# project_full_hardware.net
KiCad netlist of a schematic drawn in EAGLE
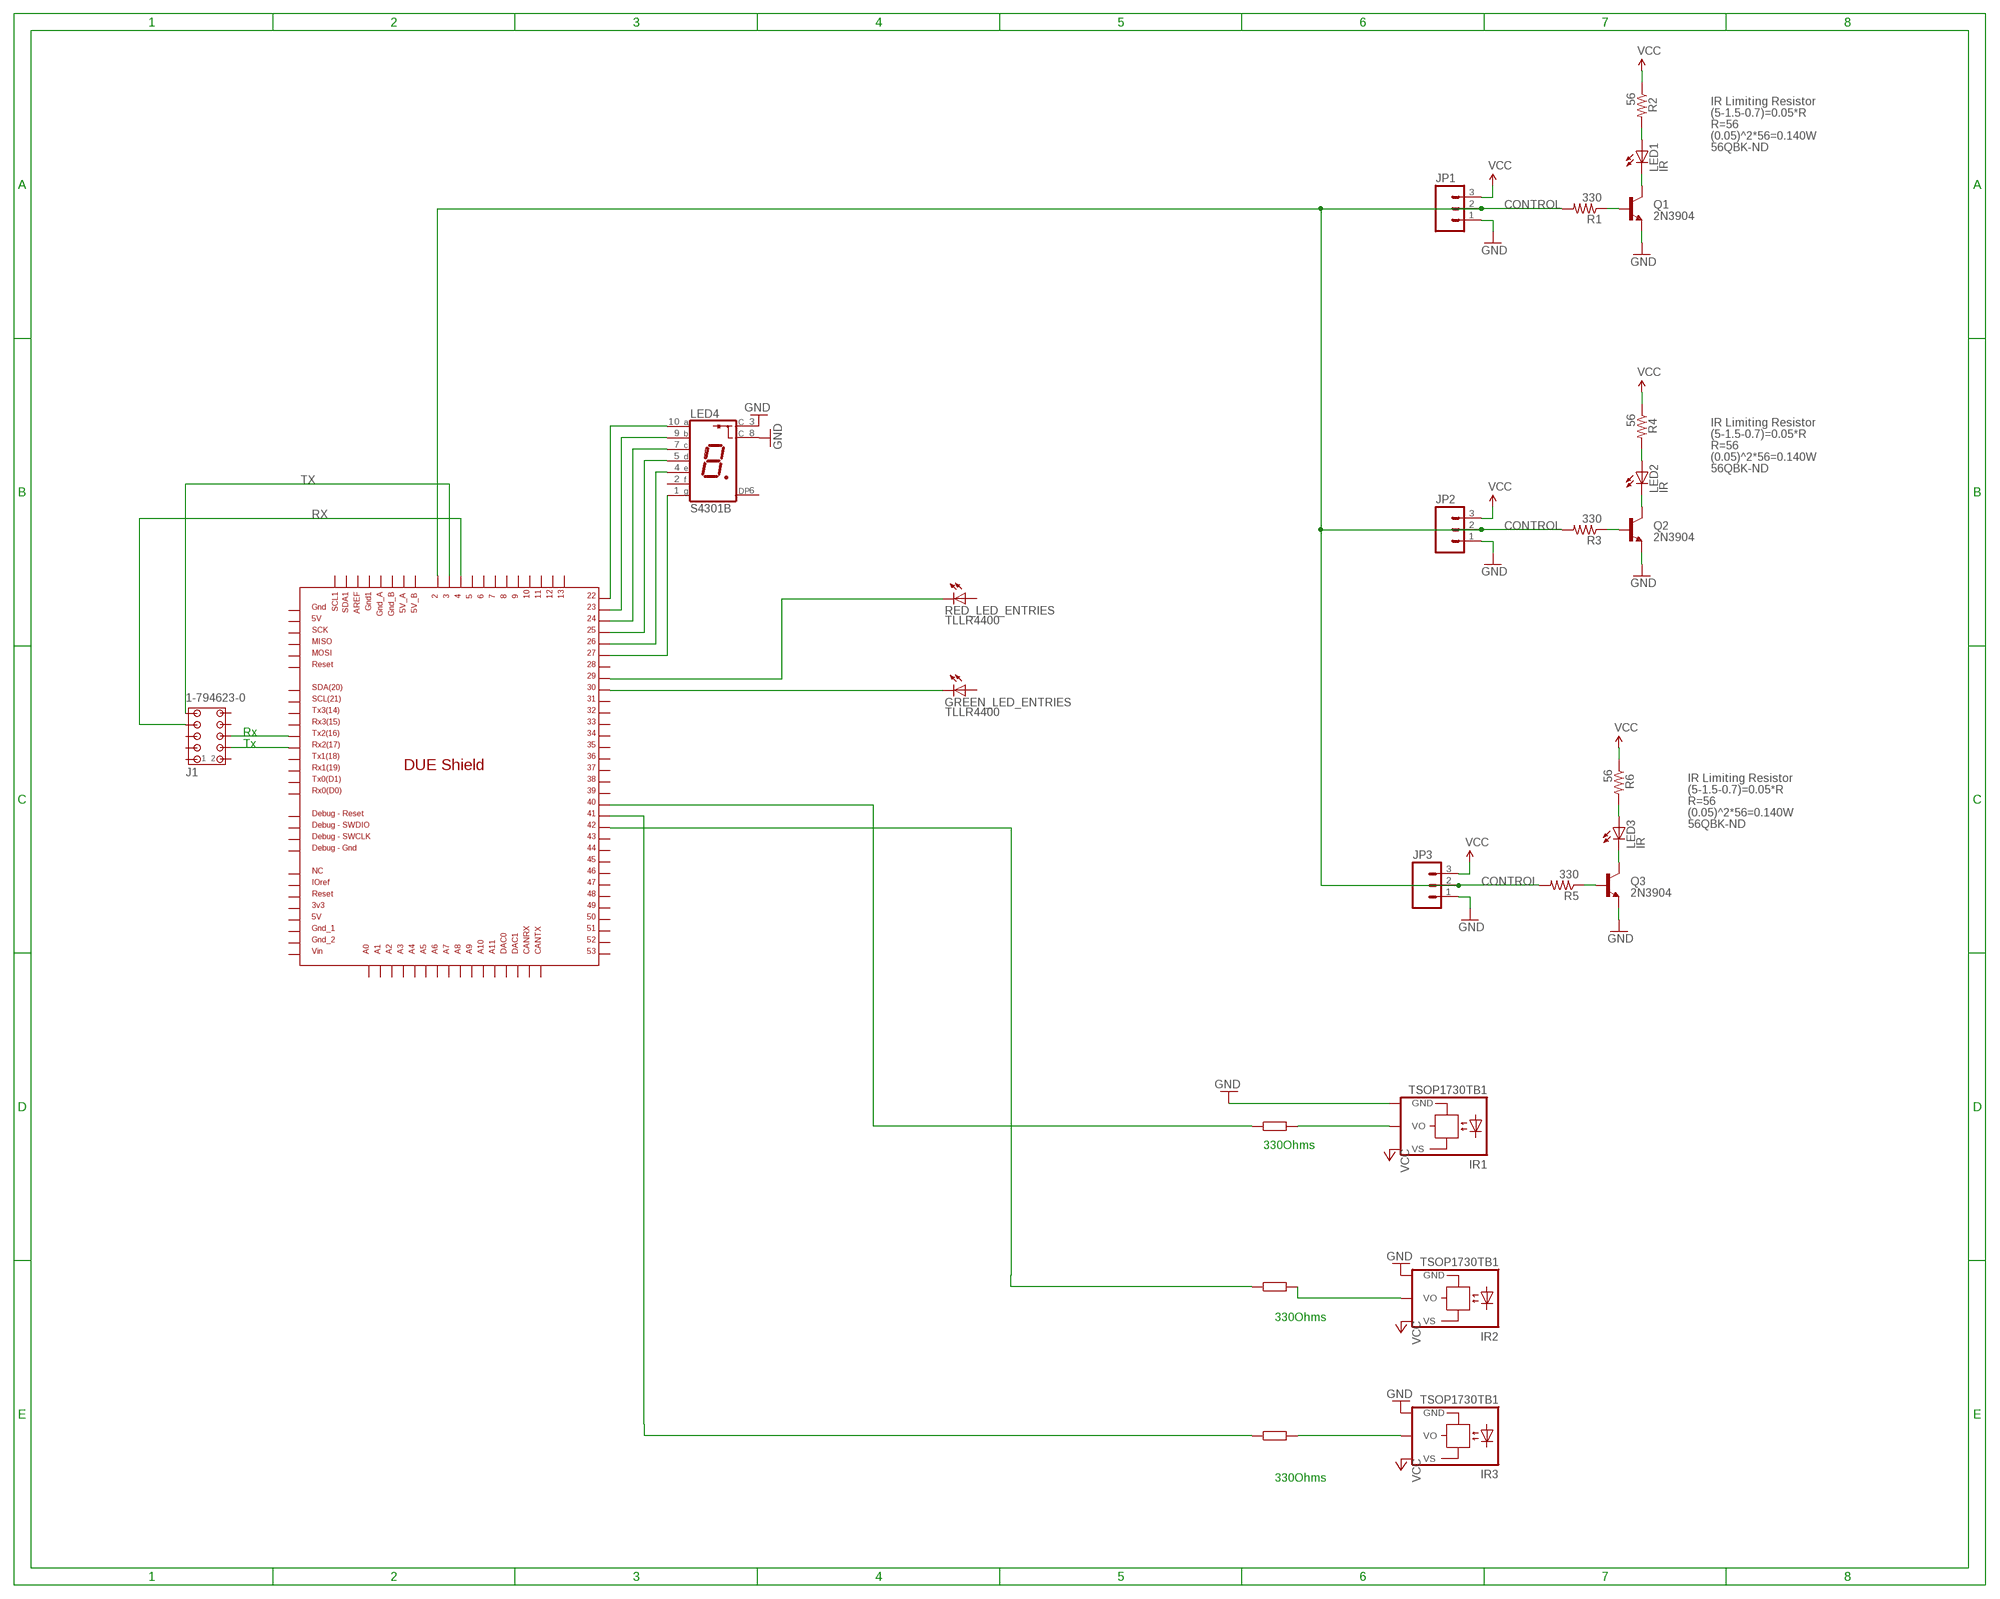
[diagram p0: schematic, sheet 1]

(export (version "E")
  (design (tool "Eeschema 10.0.6"))
  (components
    (comp (ref "GREEN_LED_ENTRIES")
      (value "TLLR4400")
      (footprint "eagle-import:LED3MM")
      (fields (field (name "MF") "VISHAY SEMICONDUCTOR"))
      (libsource (lib "eagle-import") (part "TLLR4400"))
    )
    (comp (ref "IR1")
      (value "TSOP1730TB1")
      (footprint "eagle-import:TSOP17_TB1")
      (libsource (lib "eagle-import") (part "TSOP17TB130"))
    )
    (comp (ref "IR2")
      (value "TSOP1730TB1")
      (footprint "eagle-import:TSOP17_TB1")
      (libsource (lib "eagle-import") (part "TSOP17TB130"))
    )
    (comp (ref "IR3")
      (value "TSOP1730TB1")
      (footprint "eagle-import:TSOP17_TB1")
      (libsource (lib "eagle-import") (part "TSOP17TB130"))
    )
    (comp (ref "J1")
      (value "1-794623-0")
      (footprint "eagle-import:1-794623-0")
      (libsource (lib "eagle-import") (part "1-794623-0"))
    )
    (comp (ref "JP1")
      (value "M03PTH")
      (footprint "eagle-import:1X03")
      (libsource (lib "eagle-import") (part "M03PTH"))
    )
    (comp (ref "JP2")
      (value "M03PTH")
      (footprint "eagle-import:1X03")
      (libsource (lib "eagle-import") (part "M03PTH"))
    )
    (comp (ref "JP3")
      (value "M03PTH")
      (footprint "eagle-import:1X03")
      (libsource (lib "eagle-import") (part "M03PTH"))
    )
    (comp (ref "LED1")
      (value "IR")
      (footprint "eagle-import:LED5MM")
      (libsource (lib "eagle-import") (part "LED5MM"))
    )
    (comp (ref "LED2")
      (value "IR")
      (footprint "eagle-import:LED5MM")
      (libsource (lib "eagle-import") (part "LED5MM"))
    )
    (comp (ref "LED3")
      (value "IR")
      (footprint "eagle-import:LED5MM")
      (libsource (lib "eagle-import") (part "LED5MM"))
    )
    (comp (ref "LED4")
      (value "S4301B")
      (footprint "eagle-import:S4301B")
      (libsource (lib "eagle-import") (part "S4301B"))
    )
    (comp (ref "Q1")
      (value "2N3904")
      (footprint "eagle-import:TO-92")
      (libsource (lib "eagle-import") (part "TRANSISTOR_NPNTO92"))
    )
    (comp (ref "Q2")
      (value "2N3904")
      (footprint "eagle-import:TO-92")
      (libsource (lib "eagle-import") (part "TRANSISTOR_NPNTO92"))
    )
    (comp (ref "Q3")
      (value "2N3904")
      (footprint "eagle-import:TO-92")
      (libsource (lib "eagle-import") (part "TRANSISTOR_NPNTO92"))
    )
    (comp (ref "R1")
      (value "330")
      (footprint "eagle-import:AXIAL-0.3")
      (libsource (lib "eagle-import") (part "RESISTORAXIAL-0.3"))
    )
    (comp (ref "R2")
      (value "56")
      (footprint "eagle-import:AXIAL-0.3")
      (libsource (lib "eagle-import") (part "RESISTORAXIAL-0.3"))
    )
    (comp (ref "R3")
      (value "330")
      (footprint "eagle-import:AXIAL-0.3")
      (libsource (lib "eagle-import") (part "RESISTORAXIAL-0.3"))
    )
    (comp (ref "R4")
      (value "56")
      (footprint "eagle-import:AXIAL-0.3")
      (libsource (lib "eagle-import") (part "RESISTORAXIAL-0.3"))
    )
    (comp (ref "R5")
      (value "330")
      (footprint "eagle-import:AXIAL-0.3")
      (libsource (lib "eagle-import") (part "RESISTORAXIAL-0.3"))
    )
    (comp (ref "R6")
      (value "56")
      (footprint "eagle-import:AXIAL-0.3")
      (libsource (lib "eagle-import") (part "RESISTORAXIAL-0.3"))
    )
    (comp (ref "RED_LED_ENTRIES")
      (value "TLLR4400")
      (footprint "eagle-import:LED3MM")
      (fields (field (name "MF") "VISHAY SEMICONDUCTOR"))
      (libsource (lib "eagle-import") (part "TLLR4400"))
    )
    (comp (ref "U$1")
      (value "DUE(NORMAL)")
      (footprint "eagle-import:DUE(NORMAL)")
      (libsource (lib "eagle-import") (part "DUE(NORMAL)"))
    )
  )
  (nets
    (net (code "1") (name "/CONTROL") (class "Default")
      (node (ref "JP1") (pin "2") (pinfunction "2_2") (pintype "passive"))
      (node (ref "JP2") (pin "2") (pinfunction "2_2") (pintype "passive"))
      (node (ref "JP3") (pin "2") (pinfunction "2_2") (pintype "passive"))
      (node (ref "R1") (pin "P$2") (pinfunction "2_P$2") (pintype "passive"))
      (node (ref "R3") (pin "P$2") (pinfunction "2_P$2") (pintype "passive"))
      (node (ref "R5") (pin "P$2") (pinfunction "2_P$2") (pintype "passive"))
      (node (ref "U$1") (pin "2") (pinfunction "2_2") (pintype "bidirectional"))
    )
    (net (code "2") (name "/RX") (class "Default")
      (node (ref "J1") (pin "6") (pinfunction "6_6") (pintype "passive"))
      (node (ref "J1") (pin "7") (pinfunction "7_7") (pintype "passive"))
      (node (ref "U$1") (pin "4") (pinfunction "4_4") (pintype "bidirectional"))
      (node (ref "U$1") (pin "TX2") (pinfunction "TX2_TX2") (pintype "bidirectional"))
    )
    (net (code "3") (name "/TX") (class "Default")
      (node (ref "J1") (pin "4") (pinfunction "4_4") (pintype "passive"))
      (node (ref "J1") (pin "9") (pinfunction "9_9") (pintype "passive"))
      (node (ref "U$1") (pin "3") (pinfunction "3_3") (pintype "bidirectional"))
      (node (ref "U$1") (pin "RX2") (pinfunction "RX2_RX2") (pintype "bidirectional"))
    )
    (net (code "4") (name "GND") (class "Default")
      (node (ref "IR1") (pin "GND") (pinfunction "GND_GND") (pintype "power_in"))
      (node (ref "IR2") (pin "GND") (pinfunction "GND_GND") (pintype "power_in"))
      (node (ref "IR3") (pin "GND") (pinfunction "GND_GND") (pintype "power_in"))
      (node (ref "JP1") (pin "1") (pinfunction "1_1") (pintype "passive"))
      (node (ref "JP2") (pin "1") (pinfunction "1_1") (pintype "passive"))
      (node (ref "JP3") (pin "1") (pinfunction "1_1") (pintype "passive"))
      (node (ref "LED4") (pin "3") (pinfunction "C_3") (pintype "passive"))
      (node (ref "LED4") (pin "8") (pinfunction "C_8") (pintype "passive"))
      (node (ref "Q1") (pin "1") (pinfunction "E_1") (pintype "passive"))
      (node (ref "Q2") (pin "1") (pinfunction "E_1") (pintype "passive"))
      (node (ref "Q3") (pin "1") (pinfunction "E_1") (pintype "passive"))
    )
    (net (code "5") (name "Net-(GREEN_LED_ENTRIES-C)") (class "Default")
      (node (ref "GREEN_LED_ENTRIES") (pin "K") (pinfunction "C_K") (pintype "passive"))
      (node (ref "U$1") (pin "30") (pinfunction "30_30") (pintype "bidirectional"))
    )
    (net (code "6") (name "Net-(LED1-C)") (class "Default")
      (node (ref "LED1") (pin "K") (pinfunction "C_K") (pintype "passive"))
      (node (ref "Q1") (pin "3") (pinfunction "C_3") (pintype "passive"))
    )
    (net (code "7") (name "Net-(LED2-C)") (class "Default")
      (node (ref "LED2") (pin "K") (pinfunction "C_K") (pintype "passive"))
      (node (ref "Q2") (pin "3") (pinfunction "C_3") (pintype "passive"))
    )
    (net (code "8") (name "Net-(LED3-C)") (class "Default")
      (node (ref "LED3") (pin "K") (pinfunction "C_K") (pintype "passive"))
      (node (ref "Q3") (pin "3") (pinfunction "C_3") (pintype "passive"))
    )
    (net (code "9") (name "Net-(LED4-A)") (class "Default")
      (node (ref "LED4") (pin "10") (pinfunction "A_10") (pintype "passive"))
      (node (ref "U$1") (pin "22") (pinfunction "22_22") (pintype "bidirectional"))
    )
    (net (code "10") (name "Net-(LED4-B)") (class "Default")
      (node (ref "LED4") (pin "9") (pinfunction "B_9") (pintype "passive"))
      (node (ref "U$1") (pin "23") (pinfunction "23_23") (pintype "bidirectional"))
    )
    (net (code "11") (name "Net-(LED4-C-Pad7)") (class "Default")
      (node (ref "LED4") (pin "7") (pinfunction "C_7") (pintype "passive"))
      (node (ref "U$1") (pin "24") (pinfunction "24_24") (pintype "bidirectional"))
    )
    (net (code "12") (name "Net-(LED4-D)") (class "Default")
      (node (ref "LED4") (pin "5") (pinfunction "D_5") (pintype "passive"))
      (node (ref "U$1") (pin "25") (pinfunction "25_25") (pintype "bidirectional"))
    )
    (net (code "13") (name "Net-(LED4-E)") (class "Default")
      (node (ref "LED4") (pin "4") (pinfunction "E_4") (pintype "passive"))
      (node (ref "U$1") (pin "26") (pinfunction "26_26") (pintype "bidirectional"))
    )
    (net (code "14") (name "Net-(LED4-G)") (class "Default")
      (node (ref "LED4") (pin "1") (pinfunction "G_1") (pintype "passive"))
      (node (ref "U$1") (pin "27") (pinfunction "27_27") (pintype "bidirectional"))
    )
    (net (code "15") (name "Net-(Q1-B)") (class "Default")
      (node (ref "Q1") (pin "2") (pinfunction "B_2") (pintype "passive"))
      (node (ref "R1") (pin "P$1") (pinfunction "1_P$1") (pintype "passive"))
    )
    (net (code "16") (name "Net-(Q2-B)") (class "Default")
      (node (ref "Q2") (pin "2") (pinfunction "B_2") (pintype "passive"))
      (node (ref "R3") (pin "P$1") (pinfunction "1_P$1") (pintype "passive"))
    )
    (net (code "17") (name "Net-(Q3-B)") (class "Default")
      (node (ref "Q3") (pin "2") (pinfunction "B_2") (pintype "passive"))
      (node (ref "R5") (pin "P$1") (pinfunction "1_P$1") (pintype "passive"))
    )
    (net (code "18") (name "Net-(R2-2)") (class "Default")
      (node (ref "LED1") (pin "A") (pinfunction "A_A") (pintype "passive"))
      (node (ref "R2") (pin "P$2") (pinfunction "2_P$2") (pintype "passive"))
    )
    (net (code "19") (name "Net-(R4-2)") (class "Default")
      (node (ref "LED2") (pin "A") (pinfunction "A_A") (pintype "passive"))
      (node (ref "R4") (pin "P$2") (pinfunction "2_P$2") (pintype "passive"))
    )
    (net (code "20") (name "Net-(R6-2)") (class "Default")
      (node (ref "LED3") (pin "A") (pinfunction "A_A") (pintype "passive"))
      (node (ref "R6") (pin "P$2") (pinfunction "2_P$2") (pintype "passive"))
    )
    (net (code "21") (name "Net-(RED_LED_ENTRIES-C)") (class "Default")
      (node (ref "RED_LED_ENTRIES") (pin "K") (pinfunction "C_K") (pintype "passive"))
      (node (ref "U$1") (pin "29") (pinfunction "29_29") (pintype "bidirectional"))
    )
    (net (code "22") (name "VCC") (class "Default")
      (node (ref "IR1") (pin "VS") (pinfunction "VS_VS") (pintype "power_in"))
      (node (ref "IR2") (pin "VS") (pinfunction "VS_VS") (pintype "power_in"))
      (node (ref "IR3") (pin "VS") (pinfunction "VS_VS") (pintype "power_in"))
      (node (ref "JP1") (pin "3") (pinfunction "3_3") (pintype "passive"))
      (node (ref "JP2") (pin "3") (pinfunction "3_3") (pintype "passive"))
      (node (ref "JP3") (pin "3") (pinfunction "3_3") (pintype "passive"))
      (node (ref "R2") (pin "P$1") (pinfunction "1_P$1") (pintype "passive"))
      (node (ref "R4") (pin "P$1") (pinfunction "1_P$1") (pintype "passive"))
      (node (ref "R6") (pin "P$1") (pinfunction "1_P$1") (pintype "passive"))
    )
    (net (code "23") (name "unconnected-(GREEN_LED_ENTRIES-PadA)") (class "Default")
      (node (ref "GREEN_LED_ENTRIES") (pin "A") (pinfunction "A_A") (pintype "passive"))
    )
    (net (code "24") (name "unconnected-(IR1-PadVO)") (class "Default")
      (node (ref "IR1") (pin "VO") (pinfunction "VO_VO") (pintype "open_collector"))
    )
    (net (code "25") (name "unconnected-(IR2-PadVO)") (class "Default")
      (node (ref "IR2") (pin "VO") (pinfunction "VO_VO") (pintype "open_collector"))
    )
    (net (code "26") (name "unconnected-(IR3-PadVO)") (class "Default")
      (node (ref "IR3") (pin "VO") (pinfunction "VO_VO") (pintype "open_collector"))
    )
    (net (code "27") (name "unconnected-(J1-Pad1)") (class "Default")
      (node (ref "J1") (pin "1") (pinfunction "1_1") (pintype "passive"))
    )
    (net (code "28") (name "unconnected-(J1-Pad2)") (class "Default")
      (node (ref "J1") (pin "2") (pinfunction "2_2") (pintype "passive"))
    )
    (net (code "29") (name "unconnected-(J1-Pad3)") (class "Default")
      (node (ref "J1") (pin "3") (pinfunction "3_3") (pintype "passive"))
    )
    (net (code "30") (name "unconnected-(J1-Pad5)") (class "Default")
      (node (ref "J1") (pin "5") (pinfunction "5_5") (pintype "passive"))
    )
    (net (code "31") (name "unconnected-(J1-Pad8)") (class "Default")
      (node (ref "J1") (pin "8") (pinfunction "8_8") (pintype "passive"))
    )
    (net (code "32") (name "unconnected-(J1-Pad10)") (class "Default")
      (node (ref "J1") (pin "10") (pinfunction "10_10") (pintype "passive"))
    )
    (net (code "33") (name "unconnected-(LED4-DP-Pad6)") (class "Default")
      (node (ref "LED4") (pin "6") (pinfunction "DP_6") (pintype "passive"))
    )
    (net (code "34") (name "unconnected-(LED4-F-Pad2)") (class "Default")
      (node (ref "LED4") (pin "2") (pinfunction "F_2") (pintype "passive"))
    )
    (net (code "35") (name "unconnected-(RED_LED_ENTRIES-PadA)") (class "Default")
      (node (ref "RED_LED_ENTRIES") (pin "A") (pinfunction "A_A") (pintype "passive"))
    )
    (net (code "36") (name "unconnected-(U$1-Pad3V3)") (class "Default")
      (node (ref "U$1") (pin "3V3") (pinfunction "3V3_3V3") (pintype "bidirectional"))
    )
    (net (code "37") (name "unconnected-(U$1-Pad5)") (class "Default")
      (node (ref "U$1") (pin "5") (pinfunction "5_5") (pintype "bidirectional"))
    )
    (net (code "38") (name "unconnected-(U$1-Pad5V)") (class "Default")
      (node (ref "U$1") (pin "5V") (pinfunction "5V_5V") (pintype "bidirectional"))
    )
    (net (code "39") (name "unconnected-(U$1-Pad5V_A)") (class "Default")
      (node (ref "U$1") (pin "5V_A") (pinfunction "5V_A_5V_A") (pintype "bidirectional"))
    )
    (net (code "40") (name "unconnected-(U$1-Pad5V_B)") (class "Default")
      (node (ref "U$1") (pin "5V_B") (pinfunction "5V_B_5V_B") (pintype "bidirectional"))
    )
    (net (code "41") (name "unconnected-(U$1-Pad5V_ICSP)") (class "Default")
      (node (ref "U$1") (pin "5V_ICSP") (pinfunction "5V_ICSP_5V_ICSP") (pintype "bidirectional"))
    )
    (net (code "42") (name "unconnected-(U$1-Pad6)") (class "Default")
      (node (ref "U$1") (pin "6") (pinfunction "6_6") (pintype "bidirectional"))
    )
    (net (code "43") (name "unconnected-(U$1-Pad7)") (class "Default")
      (node (ref "U$1") (pin "7") (pinfunction "7_7") (pintype "bidirectional"))
    )
    (net (code "44") (name "unconnected-(U$1-Pad8)") (class "Default")
      (node (ref "U$1") (pin "8") (pinfunction "8_8") (pintype "bidirectional"))
    )
    (net (code "45") (name "unconnected-(U$1-Pad9)") (class "Default")
      (node (ref "U$1") (pin "9") (pinfunction "9_9") (pintype "bidirectional"))
    )
    (net (code "46") (name "unconnected-(U$1-Pad10)") (class "Default")
      (node (ref "U$1") (pin "10") (pinfunction "10_10") (pintype "bidirectional"))
    )
    (net (code "47") (name "unconnected-(U$1-Pad11)") (class "Default")
      (node (ref "U$1") (pin "11") (pinfunction "11_11") (pintype "bidirectional"))
    )
    (net (code "48") (name "unconnected-(U$1-Pad12)") (class "Default")
      (node (ref "U$1") (pin "12") (pinfunction "12_12") (pintype "bidirectional"))
    )
    (net (code "49") (name "unconnected-(U$1-Pad13)") (class "Default")
      (node (ref "U$1") (pin "13") (pinfunction "13_13") (pintype "bidirectional"))
    )
    (net (code "50") (name "unconnected-(U$1-Pad28)") (class "Default")
      (node (ref "U$1") (pin "28") (pinfunction "28_28") (pintype "bidirectional"))
    )
    (net (code "51") (name "unconnected-(U$1-Pad31)") (class "Default")
      (node (ref "U$1") (pin "31") (pinfunction "31_31") (pintype "bidirectional"))
    )
    (net (code "52") (name "unconnected-(U$1-Pad32)") (class "Default")
      (node (ref "U$1") (pin "32") (pinfunction "32_32") (pintype "bidirectional"))
    )
    (net (code "53") (name "unconnected-(U$1-Pad33)") (class "Default")
      (node (ref "U$1") (pin "33") (pinfunction "33_33") (pintype "bidirectional"))
    )
    (net (code "54") (name "unconnected-(U$1-Pad34)") (class "Default")
      (node (ref "U$1") (pin "34") (pinfunction "34_34") (pintype "bidirectional"))
    )
    (net (code "55") (name "unconnected-(U$1-Pad35)") (class "Default")
      (node (ref "U$1") (pin "35") (pinfunction "35_35") (pintype "bidirectional"))
    )
    (net (code "56") (name "unconnected-(U$1-Pad36)") (class "Default")
      (node (ref "U$1") (pin "36") (pinfunction "36_36") (pintype "bidirectional"))
    )
    (net (code "57") (name "unconnected-(U$1-Pad37)") (class "Default")
      (node (ref "U$1") (pin "37") (pinfunction "37_37") (pintype "bidirectional"))
    )
    (net (code "58") (name "unconnected-(U$1-Pad38)") (class "Default")
      (node (ref "U$1") (pin "38") (pinfunction "38_38") (pintype "bidirectional"))
    )
    (net (code "59") (name "unconnected-(U$1-Pad39)") (class "Default")
      (node (ref "U$1") (pin "39") (pinfunction "39_39") (pintype "bidirectional"))
    )
    (net (code "60") (name "unconnected-(U$1-Pad40)") (class "Default")
      (node (ref "U$1") (pin "40") (pinfunction "40_40") (pintype "bidirectional"))
    )
    (net (code "61") (name "unconnected-(U$1-Pad41)") (class "Default")
      (node (ref "U$1") (pin "41") (pinfunction "41_41") (pintype "bidirectional"))
    )
    (net (code "62") (name "unconnected-(U$1-Pad42)") (class "Default")
      (node (ref "U$1") (pin "42") (pinfunction "42_42") (pintype "bidirectional"))
    )
    (net (code "63") (name "unconnected-(U$1-Pad43)") (class "Default")
      (node (ref "U$1") (pin "43") (pinfunction "43_43") (pintype "bidirectional"))
    )
    (net (code "64") (name "unconnected-(U$1-Pad44)") (class "Default")
      (node (ref "U$1") (pin "44") (pinfunction "44_44") (pintype "bidirectional"))
    )
    (net (code "65") (name "unconnected-(U$1-Pad45)") (class "Default")
      (node (ref "U$1") (pin "45") (pinfunction "45_45") (pintype "bidirectional"))
    )
    (net (code "66") (name "unconnected-(U$1-Pad46)") (class "Default")
      (node (ref "U$1") (pin "46") (pinfunction "46_46") (pintype "bidirectional"))
    )
    (net (code "67") (name "unconnected-(U$1-Pad47)") (class "Default")
      (node (ref "U$1") (pin "47") (pinfunction "47_47") (pintype "bidirectional"))
    )
    (net (code "68") (name "unconnected-(U$1-Pad48)") (class "Default")
      (node (ref "U$1") (pin "48") (pinfunction "48_48") (pintype "bidirectional"))
    )
    (net (code "69") (name "unconnected-(U$1-Pad49)") (class "Default")
      (node (ref "U$1") (pin "49") (pinfunction "49_49") (pintype "bidirectional"))
    )
    (net (code "70") (name "unconnected-(U$1-Pad50)") (class "Default")
      (node (ref "U$1") (pin "50") (pinfunction "50_50") (pintype "bidirectional"))
    )
    (net (code "71") (name "unconnected-(U$1-Pad51)") (class "Default")
      (node (ref "U$1") (pin "51") (pinfunction "51_51") (pintype "bidirectional"))
    )
    (net (code "72") (name "unconnected-(U$1-Pad52)") (class "Default")
      (node (ref "U$1") (pin "52") (pinfunction "52_52") (pintype "bidirectional"))
    )
    (net (code "73") (name "unconnected-(U$1-Pad53)") (class "Default")
      (node (ref "U$1") (pin "53") (pinfunction "53_53") (pintype "bidirectional"))
    )
    (net (code "74") (name "unconnected-(U$1-PadA0)") (class "Default")
      (node (ref "U$1") (pin "A0") (pinfunction "A0_A0") (pintype "bidirectional"))
    )
    (net (code "75") (name "unconnected-(U$1-PadA1)") (class "Default")
      (node (ref "U$1") (pin "A1") (pinfunction "A1_A1") (pintype "bidirectional"))
    )
    (net (code "76") (name "unconnected-(U$1-PadA2)") (class "Default")
      (node (ref "U$1") (pin "A2") (pinfunction "A2_A2") (pintype "bidirectional"))
    )
    (net (code "77") (name "unconnected-(U$1-PadA3)") (class "Default")
      (node (ref "U$1") (pin "A3") (pinfunction "A3_A3") (pintype "bidirectional"))
    )
    (net (code "78") (name "unconnected-(U$1-PadA4)") (class "Default")
      (node (ref "U$1") (pin "A4") (pinfunction "A4_A4") (pintype "bidirectional"))
    )
    (net (code "79") (name "unconnected-(U$1-PadA5)") (class "Default")
      (node (ref "U$1") (pin "A5") (pinfunction "A5_A5") (pintype "bidirectional"))
    )
    (net (code "80") (name "unconnected-(U$1-PadA6)") (class "Default")
      (node (ref "U$1") (pin "A6") (pinfunction "A6_A6") (pintype "bidirectional"))
    )
    (net (code "81") (name "unconnected-(U$1-PadA7)") (class "Default")
      (node (ref "U$1") (pin "A7") (pinfunction "A7_A7") (pintype "bidirectional"))
    )
    (net (code "82") (name "unconnected-(U$1-PadA8)") (class "Default")
      (node (ref "U$1") (pin "A8") (pinfunction "A8_A8") (pintype "bidirectional"))
    )
    (net (code "83") (name "unconnected-(U$1-PadA9)") (class "Default")
      (node (ref "U$1") (pin "A9") (pinfunction "A9_A9") (pintype "bidirectional"))
    )
    (net (code "84") (name "unconnected-(U$1-PadA10)") (class "Default")
      (node (ref "U$1") (pin "A10") (pinfunction "A10_A10") (pintype "bidirectional"))
    )
    (net (code "85") (name "unconnected-(U$1-PadA11)") (class "Default")
      (node (ref "U$1") (pin "A11") (pinfunction "A11_A11") (pintype "bidirectional"))
    )
    (net (code "86") (name "unconnected-(U$1-PadAREF)") (class "Default")
      (node (ref "U$1") (pin "AREF") (pinfunction "AREF_AREF") (pintype "bidirectional"))
    )
    (net (code "87") (name "unconnected-(U$1-PadCANRX)") (class "Default")
      (node (ref "U$1") (pin "CANRX") (pinfunction "CANRX_CANRX") (pintype "bidirectional"))
    )
    (net (code "88") (name "unconnected-(U$1-PadCANTX)") (class "Default")
      (node (ref "U$1") (pin "CANTX") (pinfunction "CANTX_CANTX") (pintype "bidirectional"))
    )
    (net (code "89") (name "unconnected-(U$1-PadDAC0)") (class "Default")
      (node (ref "U$1") (pin "DAC0") (pinfunction "DAC0_DAC0") (pintype "bidirectional"))
    )
    (net (code "90") (name "unconnected-(U$1-PadDAC1)") (class "Default")
      (node (ref "U$1") (pin "DAC1") (pinfunction "DAC1_DAC1") (pintype "bidirectional"))
    )
    (net (code "91") (name "unconnected-(U$1-PadGND1)") (class "Default")
      (node (ref "U$1") (pin "GND1") (pinfunction "GND1_GND1") (pintype "bidirectional"))
    )
    (net (code "92") (name "unconnected-(U$1-PadGND_1)") (class "Default")
      (node (ref "U$1") (pin "GND_1") (pinfunction "GND_1_GND_1") (pintype "bidirectional"))
    )
    (net (code "93") (name "unconnected-(U$1-PadGND_2)") (class "Default")
      (node (ref "U$1") (pin "GND_2") (pinfunction "GND_2_GND_2") (pintype "bidirectional"))
    )
    (net (code "94") (name "unconnected-(U$1-PadGND_A)") (class "Default")
      (node (ref "U$1") (pin "GND_A") (pinfunction "GND_A_GND_A") (pintype "bidirectional"))
    )
    (net (code "95") (name "unconnected-(U$1-PadGND_B)") (class "Default")
      (node (ref "U$1") (pin "GND_B") (pinfunction "GND_B_GND_B") (pintype "bidirectional"))
    )
    (net (code "96") (name "unconnected-(U$1-PadGND_DEBUG)") (class "Default")
      (node (ref "U$1") (pin "GND_DEBUG") (pinfunction "GND_DEBUG_GND_DEBUG") (pintype "bidirectional"))
    )
    (net (code "97") (name "unconnected-(U$1-PadGND_ICSP)") (class "Default")
      (node (ref "U$1") (pin "GND_ICSP") (pinfunction "GND_ICSP_GND_ICSP") (pintype "bidirectional"))
    )
    (net (code "98") (name "unconnected-(U$1-PadIOREF)") (class "Default")
      (node (ref "U$1") (pin "IOREF") (pinfunction "IOREF_IOREF") (pintype "bidirectional"))
    )
    (net (code "99") (name "unconnected-(U$1-PadMISO_ICSP)") (class "Default")
      (node (ref "U$1") (pin "MISO_ICSP") (pinfunction "MISO_ICSP_MISO_ICSP") (pintype "bidirectional"))
    )
    (net (code "100") (name "unconnected-(U$1-PadMOSI_ICSP)") (class "Default")
      (node (ref "U$1") (pin "MOSI_ICSP") (pinfunction "MOSI_ICSP_MOSI_ICSP") (pintype "bidirectional"))
    )
    (net (code "101") (name "unconnected-(U$1-PadNC)") (class "Default")
      (node (ref "U$1") (pin "NC") (pinfunction "NC_NC") (pintype "bidirectional"))
    )
    (net (code "102") (name "unconnected-(U$1-PadRESET)") (class "Default")
      (node (ref "U$1") (pin "RESET") (pinfunction "RESET_RESET") (pintype "bidirectional"))
    )
    (net (code "103") (name "unconnected-(U$1-PadRESET_DEBUG)") (class "Default")
      (node (ref "U$1") (pin "RESET_DEBUG") (pinfunction "RESET_DEBUG_RESET_DEBUG") (pintype "bidirectional"))
    )
    (net (code "104") (name "unconnected-(U$1-PadRESET_ICSP)") (class "Default")
      (node (ref "U$1") (pin "RESET_ICSP") (pinfunction "RESET_ICSP_RESET_ICSP") (pintype "bidirectional"))
    )
    (net (code "105") (name "unconnected-(U$1-PadRX0)") (class "Default")
      (node (ref "U$1") (pin "RX0") (pinfunction "RX0_RX0") (pintype "bidirectional"))
    )
    (net (code "106") (name "unconnected-(U$1-PadRX1)") (class "Default")
      (node (ref "U$1") (pin "RX1") (pinfunction "RX1_RX1") (pintype "bidirectional"))
    )
    (net (code "107") (name "unconnected-(U$1-PadRX3)") (class "Default")
      (node (ref "U$1") (pin "RX3") (pinfunction "RX3_RX3") (pintype "bidirectional"))
    )
    (net (code "108") (name "unconnected-(U$1-PadSCK_ICSP)") (class "Default")
      (node (ref "U$1") (pin "SCK_ICSP") (pinfunction "SCK_ICSP_SCK_ICSP") (pintype "bidirectional"))
    )
    (net (code "109") (name "unconnected-(U$1-PadSCL)") (class "Default")
      (node (ref "U$1") (pin "SCL") (pinfunction "SCL_SCL") (pintype "bidirectional"))
    )
    (net (code "110") (name "unconnected-(U$1-PadSCL1)") (class "Default")
      (node (ref "U$1") (pin "SCL1") (pinfunction "SCL1_SCL1") (pintype "bidirectional"))
    )
    (net (code "111") (name "unconnected-(U$1-PadSDA)") (class "Default")
      (node (ref "U$1") (pin "SDA") (pinfunction "SDA_SDA") (pintype "bidirectional"))
    )
    (net (code "112") (name "unconnected-(U$1-PadSDA1)") (class "Default")
      (node (ref "U$1") (pin "SDA1") (pinfunction "SDA1_SDA1") (pintype "bidirectional"))
    )
    (net (code "113") (name "unconnected-(U$1-PadSWCLK_DEBUG)") (class "Default")
      (node (ref "U$1") (pin "SWCLK_DEBUG") (pinfunction "SWCLK_DEBUG_SWCLK_DEBUG") (pintype "bidirectional"))
    )
    (net (code "114") (name "unconnected-(U$1-PadSWDIO_DEBUG)") (class "Default")
      (node (ref "U$1") (pin "SWDIO_DEBUG") (pinfunction "SWDIO_DEBUG_SWDIO_DEBUG") (pintype "bidirectional"))
    )
    (net (code "115") (name "unconnected-(U$1-PadTX0)") (class "Default")
      (node (ref "U$1") (pin "TX0") (pinfunction "TX0_TX0") (pintype "bidirectional"))
    )
    (net (code "116") (name "unconnected-(U$1-PadTX1)") (class "Default")
      (node (ref "U$1") (pin "TX1") (pinfunction "TX1_TX1") (pintype "bidirectional"))
    )
    (net (code "117") (name "unconnected-(U$1-PadTX3)") (class "Default")
      (node (ref "U$1") (pin "TX3") (pinfunction "TX3_TX3") (pintype "bidirectional"))
    )
    (net (code "118") (name "unconnected-(U$1-PadVIN)") (class "Default")
      (node (ref "U$1") (pin "VIN") (pinfunction "VIN_VIN") (pintype "bidirectional"))
    )
  )
)
